# TFT_Interface.net
KiCad netlist of a schematic drawn in EAGLE
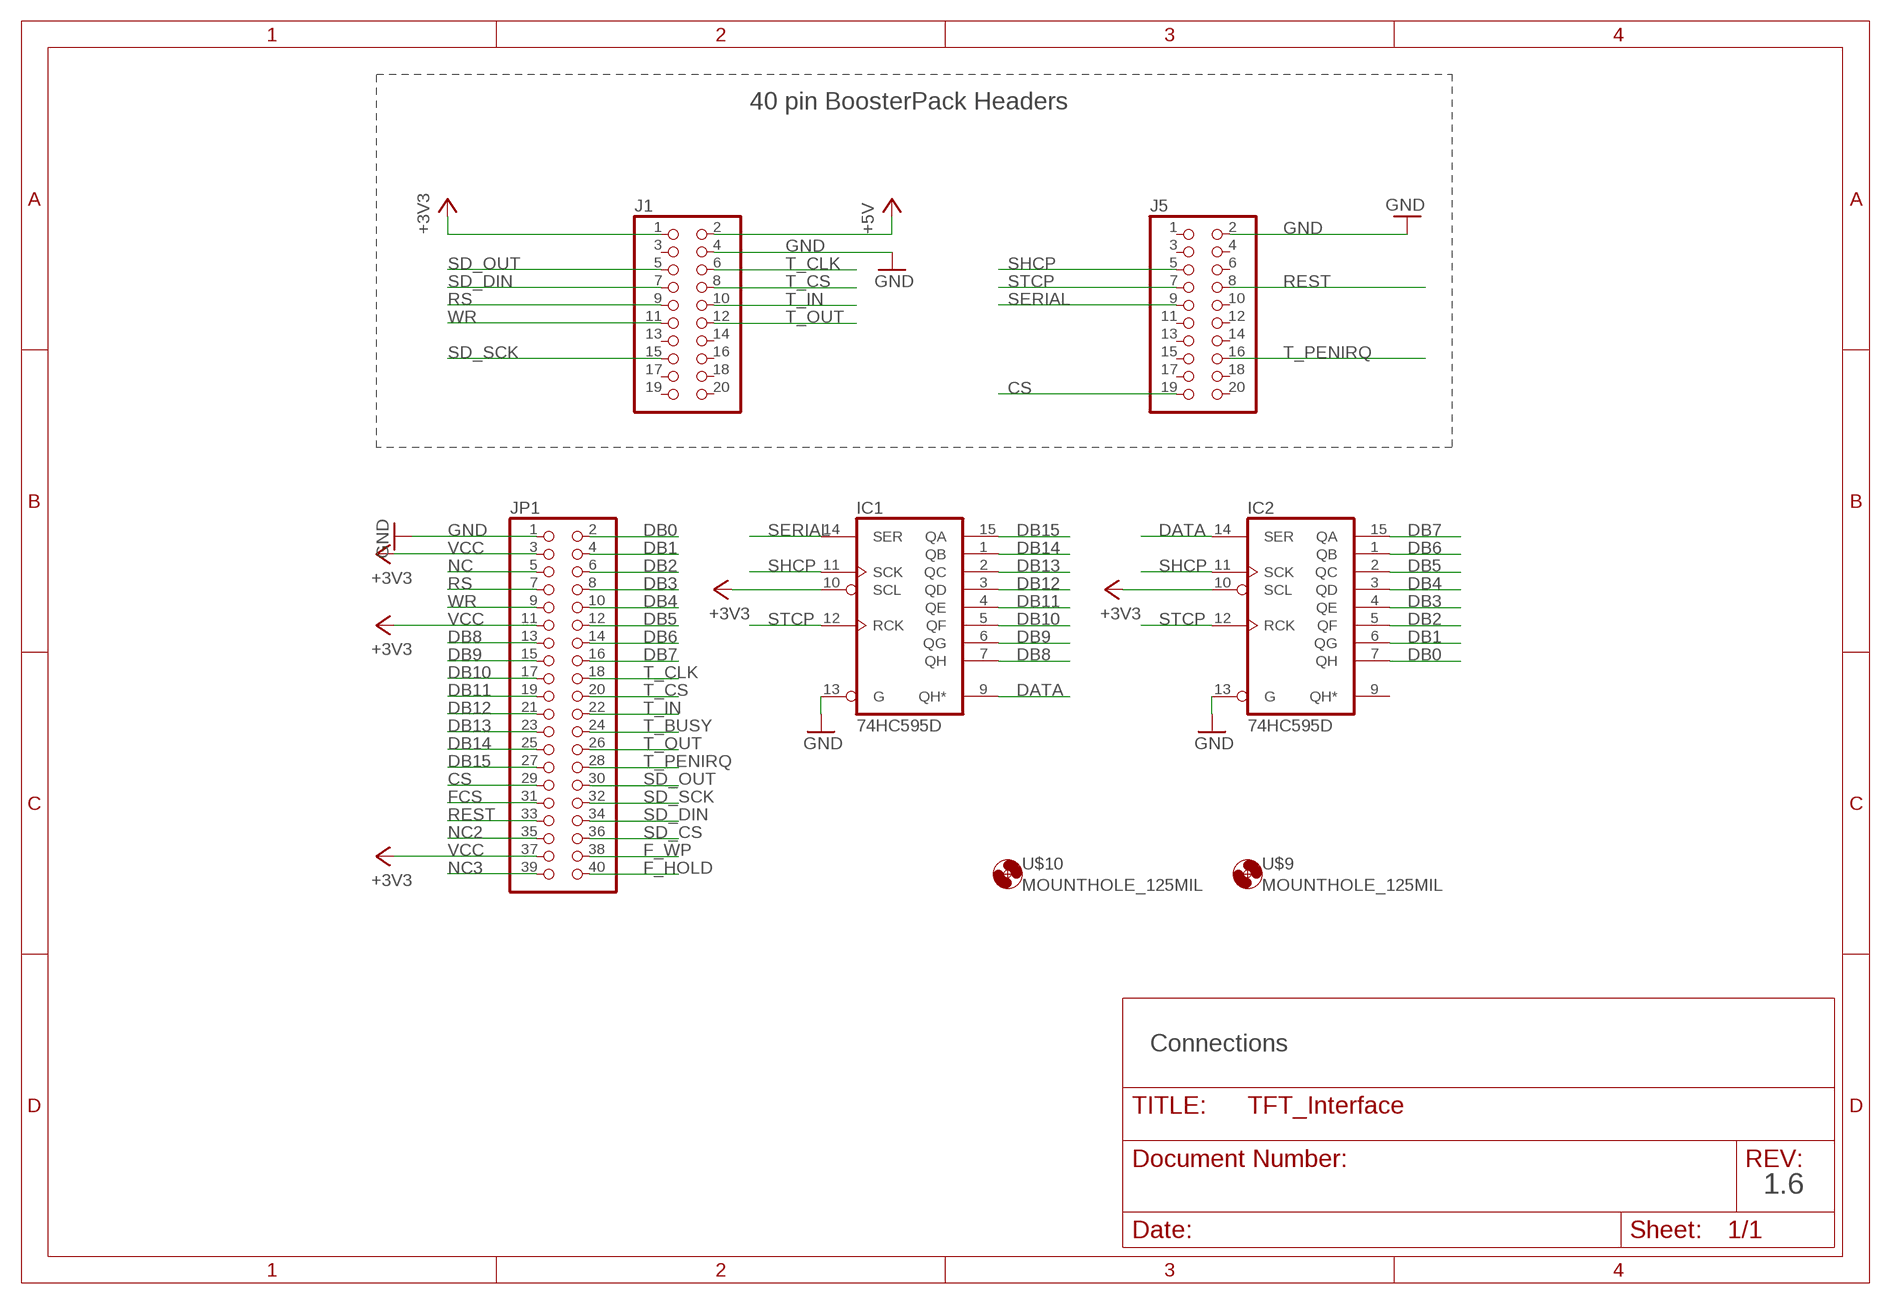
[diagram p0: schematic, sheet 1]

(export (version "E")
  (design (tool "Eeschema 10.0.6"))
  (components
    (comp (ref "IC1")
      (value "74HC595D")
      (footprint "eagle-import:SO16")
      (libsource (lib "eagle-import") (part "74595DHC"))
    )
    (comp (ref "IC2")
      (value "74HC595D")
      (footprint "eagle-import:SO16")
      (libsource (lib "eagle-import") (part "74595DHC"))
    )
    (comp (ref "J1")
      (value "PINHD-2X10")
      (footprint "eagle-import:2X10")
      (libsource (lib "eagle-import") (part "PINHD-2X10"))
    )
    (comp (ref "J5")
      (value "PINHD-2X10")
      (footprint "eagle-import:2X10")
      (libsource (lib "eagle-import") (part "PINHD-2X10"))
    )
    (comp (ref "JP1")
      (value "PINHD-2X20")
      (footprint "eagle-import:2X20")
      (libsource (lib "eagle-import") (part "PINHD-2X20"))
    )
    (comp (ref "U$9")
      (value "MOUNTHOLE_125MIL")
      (footprint "eagle-import:MOUNTHOLE_125MIL")
      (libsource (lib "eagle-import") (part "MOUNTHOLE_125MIL"))
    )
    (comp (ref "U$10")
      (value "MOUNTHOLE_125MIL")
      (footprint "eagle-import:MOUNTHOLE_125MIL")
      (libsource (lib "eagle-import") (part "MOUNTHOLE_125MIL"))
    )
  )
  (nets
    (net (code "1") (name "+3V3") (class "Default")
      (node (ref "IC1") (pin "10") (pinfunction "SCL_10") (pintype "input"))
      (node (ref "IC2") (pin "10") (pinfunction "SCL_10") (pintype "input"))
      (node (ref "J1") (pin "1") (pinfunction "1_1") (pintype "passive"))
      (node (ref "JP1") (pin "11") (pinfunction "11_11") (pintype "passive"))
      (node (ref "JP1") (pin "3") (pinfunction "3_3") (pintype "passive"))
      (node (ref "JP1") (pin "37") (pinfunction "37_37") (pintype "passive"))
    )
    (net (code "2") (name "+5V") (class "Default")
      (node (ref "J1") (pin "2") (pinfunction "2_2") (pintype "passive"))
    )
    (net (code "3") (name "/CS") (class "Default")
      (node (ref "J5") (pin "19") (pinfunction "19_19") (pintype "passive"))
      (node (ref "JP1") (pin "29") (pinfunction "29_29") (pintype "passive"))
    )
    (net (code "4") (name "/DATA") (class "Default")
      (node (ref "IC1") (pin "9") (pinfunction "QH*_9") (pintype "tri_state"))
      (node (ref "IC2") (pin "14") (pinfunction "SER_14") (pintype "input"))
    )
    (net (code "5") (name "/DB0") (class "Default")
      (node (ref "IC2") (pin "7") (pinfunction "QH_7") (pintype "tri_state"))
      (node (ref "JP1") (pin "2") (pinfunction "2_2") (pintype "passive"))
    )
    (net (code "6") (name "/DB1") (class "Default")
      (node (ref "IC2") (pin "6") (pinfunction "QG_6") (pintype "tri_state"))
      (node (ref "JP1") (pin "4") (pinfunction "4_4") (pintype "passive"))
    )
    (net (code "7") (name "/DB2") (class "Default")
      (node (ref "IC2") (pin "5") (pinfunction "QF_5") (pintype "tri_state"))
      (node (ref "JP1") (pin "6") (pinfunction "6_6") (pintype "passive"))
    )
    (net (code "8") (name "/DB3") (class "Default")
      (node (ref "IC2") (pin "4") (pinfunction "QE_4") (pintype "tri_state"))
      (node (ref "JP1") (pin "8") (pinfunction "8_8") (pintype "passive"))
    )
    (net (code "9") (name "/DB4") (class "Default")
      (node (ref "IC2") (pin "3") (pinfunction "QD_3") (pintype "tri_state"))
      (node (ref "JP1") (pin "10") (pinfunction "10_10") (pintype "passive"))
    )
    (net (code "10") (name "/DB5") (class "Default")
      (node (ref "IC2") (pin "2") (pinfunction "QC_2") (pintype "tri_state"))
      (node (ref "JP1") (pin "12") (pinfunction "12_12") (pintype "passive"))
    )
    (net (code "11") (name "/DB6") (class "Default")
      (node (ref "IC2") (pin "1") (pinfunction "QB_1") (pintype "tri_state"))
      (node (ref "JP1") (pin "14") (pinfunction "14_14") (pintype "passive"))
    )
    (net (code "12") (name "/DB7") (class "Default")
      (node (ref "IC2") (pin "15") (pinfunction "QA_15") (pintype "tri_state"))
      (node (ref "JP1") (pin "16") (pinfunction "16_16") (pintype "passive"))
    )
    (net (code "13") (name "/DB8") (class "Default")
      (node (ref "IC1") (pin "7") (pinfunction "QH_7") (pintype "tri_state"))
      (node (ref "JP1") (pin "13") (pinfunction "13_13") (pintype "passive"))
    )
    (net (code "14") (name "/DB9") (class "Default")
      (node (ref "IC1") (pin "6") (pinfunction "QG_6") (pintype "tri_state"))
      (node (ref "JP1") (pin "15") (pinfunction "15_15") (pintype "passive"))
    )
    (net (code "15") (name "/DB10") (class "Default")
      (node (ref "IC1") (pin "5") (pinfunction "QF_5") (pintype "tri_state"))
      (node (ref "JP1") (pin "17") (pinfunction "17_17") (pintype "passive"))
    )
    (net (code "16") (name "/DB11") (class "Default")
      (node (ref "IC1") (pin "4") (pinfunction "QE_4") (pintype "tri_state"))
      (node (ref "JP1") (pin "19") (pinfunction "19_19") (pintype "passive"))
    )
    (net (code "17") (name "/DB12") (class "Default")
      (node (ref "IC1") (pin "3") (pinfunction "QD_3") (pintype "tri_state"))
      (node (ref "JP1") (pin "21") (pinfunction "21_21") (pintype "passive"))
    )
    (net (code "18") (name "/DB13") (class "Default")
      (node (ref "IC1") (pin "2") (pinfunction "QC_2") (pintype "tri_state"))
      (node (ref "JP1") (pin "23") (pinfunction "23_23") (pintype "passive"))
    )
    (net (code "19") (name "/DB14") (class "Default")
      (node (ref "IC1") (pin "1") (pinfunction "QB_1") (pintype "tri_state"))
      (node (ref "JP1") (pin "25") (pinfunction "25_25") (pintype "passive"))
    )
    (net (code "20") (name "/DB15") (class "Default")
      (node (ref "IC1") (pin "15") (pinfunction "QA_15") (pintype "tri_state"))
      (node (ref "JP1") (pin "27") (pinfunction "27_27") (pintype "passive"))
    )
    (net (code "21") (name "/FCS") (class "Default")
      (node (ref "JP1") (pin "31") (pinfunction "31_31") (pintype "passive"))
    )
    (net (code "22") (name "/F_HOLD") (class "Default")
      (node (ref "JP1") (pin "40") (pinfunction "40_40") (pintype "passive"))
    )
    (net (code "23") (name "/F_WP") (class "Default")
      (node (ref "JP1") (pin "38") (pinfunction "38_38") (pintype "passive"))
    )
    (net (code "24") (name "/NC") (class "Default")
      (node (ref "JP1") (pin "5") (pinfunction "5_5") (pintype "passive"))
    )
    (net (code "25") (name "/NC2") (class "Default")
      (node (ref "JP1") (pin "35") (pinfunction "35_35") (pintype "passive"))
    )
    (net (code "26") (name "/NC3") (class "Default")
      (node (ref "JP1") (pin "39") (pinfunction "39_39") (pintype "passive"))
    )
    (net (code "27") (name "/REST") (class "Default")
      (node (ref "J5") (pin "8") (pinfunction "8_8") (pintype "passive"))
      (node (ref "JP1") (pin "33") (pinfunction "33_33") (pintype "passive"))
    )
    (net (code "28") (name "/RS") (class "Default")
      (node (ref "J1") (pin "9") (pinfunction "9_9") (pintype "passive"))
      (node (ref "JP1") (pin "7") (pinfunction "7_7") (pintype "passive"))
    )
    (net (code "29") (name "/SD_CS") (class "Default")
      (node (ref "JP1") (pin "36") (pinfunction "36_36") (pintype "passive"))
    )
    (net (code "30") (name "/SD_DIN") (class "Default")
      (node (ref "J1") (pin "7") (pinfunction "7_7") (pintype "passive"))
      (node (ref "JP1") (pin "34") (pinfunction "34_34") (pintype "passive"))
    )
    (net (code "31") (name "/SD_OUT") (class "Default")
      (node (ref "J1") (pin "5") (pinfunction "5_5") (pintype "passive"))
      (node (ref "JP1") (pin "30") (pinfunction "30_30") (pintype "passive"))
    )
    (net (code "32") (name "/SD_SCK") (class "Default")
      (node (ref "J1") (pin "15") (pinfunction "15_15") (pintype "passive"))
      (node (ref "JP1") (pin "32") (pinfunction "32_32") (pintype "passive"))
    )
    (net (code "33") (name "/SERIAL") (class "Default")
      (node (ref "IC1") (pin "14") (pinfunction "SER_14") (pintype "input"))
      (node (ref "J5") (pin "9") (pinfunction "9_9") (pintype "passive"))
    )
    (net (code "34") (name "/SHCP") (class "Default")
      (node (ref "IC1") (pin "11") (pinfunction "SCK_11") (pintype "input"))
      (node (ref "IC2") (pin "11") (pinfunction "SCK_11") (pintype "input"))
      (node (ref "J5") (pin "5") (pinfunction "5_5") (pintype "passive"))
    )
    (net (code "35") (name "/STCP") (class "Default")
      (node (ref "IC1") (pin "12") (pinfunction "RCK_12") (pintype "input"))
      (node (ref "IC2") (pin "12") (pinfunction "RCK_12") (pintype "input"))
      (node (ref "J5") (pin "7") (pinfunction "7_7") (pintype "passive"))
    )
    (net (code "36") (name "/T_BUSY") (class "Default")
      (node (ref "JP1") (pin "24") (pinfunction "24_24") (pintype "passive"))
    )
    (net (code "37") (name "/T_CLK") (class "Default")
      (node (ref "J1") (pin "6") (pinfunction "6_6") (pintype "passive"))
      (node (ref "JP1") (pin "18") (pinfunction "18_18") (pintype "passive"))
    )
    (net (code "38") (name "/T_CS") (class "Default")
      (node (ref "J1") (pin "8") (pinfunction "8_8") (pintype "passive"))
      (node (ref "JP1") (pin "20") (pinfunction "20_20") (pintype "passive"))
    )
    (net (code "39") (name "/T_IN") (class "Default")
      (node (ref "J1") (pin "10") (pinfunction "10_10") (pintype "passive"))
      (node (ref "JP1") (pin "22") (pinfunction "22_22") (pintype "passive"))
    )
    (net (code "40") (name "/T_OUT") (class "Default")
      (node (ref "J1") (pin "12") (pinfunction "12_12") (pintype "passive"))
      (node (ref "JP1") (pin "26") (pinfunction "26_26") (pintype "passive"))
    )
    (net (code "41") (name "/T_PENIRQ") (class "Default")
      (node (ref "J5") (pin "16") (pinfunction "16_16") (pintype "passive"))
      (node (ref "JP1") (pin "28") (pinfunction "28_28") (pintype "passive"))
    )
    (net (code "42") (name "/WR") (class "Default")
      (node (ref "J1") (pin "11") (pinfunction "11_11") (pintype "passive"))
      (node (ref "JP1") (pin "9") (pinfunction "9_9") (pintype "passive"))
    )
    (net (code "43") (name "GND") (class "Default")
      (node (ref "IC1") (pin "13") (pinfunction "G_13") (pintype "input"))
      (node (ref "IC2") (pin "13") (pinfunction "G_13") (pintype "input"))
      (node (ref "J1") (pin "4") (pinfunction "4_4") (pintype "passive"))
      (node (ref "J5") (pin "2") (pinfunction "2_2") (pintype "passive"))
      (node (ref "JP1") (pin "1") (pinfunction "1_1") (pintype "passive"))
    )
    (net (code "44") (name "unconnected-(IC2A-QH*-Pad9)") (class "Default")
      (node (ref "IC2") (pin "9") (pinfunction "QH*_9") (pintype "tri_state"))
    )
    (net (code "45") (name "unconnected-(J1-Pad3)") (class "Default")
      (node (ref "J1") (pin "3") (pinfunction "3_3") (pintype "passive"))
    )
    (net (code "46") (name "unconnected-(J1-Pad13)") (class "Default")
      (node (ref "J1") (pin "13") (pinfunction "13_13") (pintype "passive"))
    )
    (net (code "47") (name "unconnected-(J1-Pad14)") (class "Default")
      (node (ref "J1") (pin "14") (pinfunction "14_14") (pintype "passive"))
    )
    (net (code "48") (name "unconnected-(J1-Pad16)") (class "Default")
      (node (ref "J1") (pin "16") (pinfunction "16_16") (pintype "passive"))
    )
    (net (code "49") (name "unconnected-(J1-Pad17)") (class "Default")
      (node (ref "J1") (pin "17") (pinfunction "17_17") (pintype "passive"))
    )
    (net (code "50") (name "unconnected-(J1-Pad18)") (class "Default")
      (node (ref "J1") (pin "18") (pinfunction "18_18") (pintype "passive"))
    )
    (net (code "51") (name "unconnected-(J1-Pad19)") (class "Default")
      (node (ref "J1") (pin "19") (pinfunction "19_19") (pintype "passive"))
    )
    (net (code "52") (name "unconnected-(J1-Pad20)") (class "Default")
      (node (ref "J1") (pin "20") (pinfunction "20_20") (pintype "passive"))
    )
    (net (code "53") (name "unconnected-(J5-Pad1)") (class "Default")
      (node (ref "J5") (pin "1") (pinfunction "1_1") (pintype "passive"))
    )
    (net (code "54") (name "unconnected-(J5-Pad3)") (class "Default")
      (node (ref "J5") (pin "3") (pinfunction "3_3") (pintype "passive"))
    )
    (net (code "55") (name "unconnected-(J5-Pad4)") (class "Default")
      (node (ref "J5") (pin "4") (pinfunction "4_4") (pintype "passive"))
    )
    (net (code "56") (name "unconnected-(J5-Pad6)") (class "Default")
      (node (ref "J5") (pin "6") (pinfunction "6_6") (pintype "passive"))
    )
    (net (code "57") (name "unconnected-(J5-Pad10)") (class "Default")
      (node (ref "J5") (pin "10") (pinfunction "10_10") (pintype "passive"))
    )
    (net (code "58") (name "unconnected-(J5-Pad11)") (class "Default")
      (node (ref "J5") (pin "11") (pinfunction "11_11") (pintype "passive"))
    )
    (net (code "59") (name "unconnected-(J5-Pad12)") (class "Default")
      (node (ref "J5") (pin "12") (pinfunction "12_12") (pintype "passive"))
    )
    (net (code "60") (name "unconnected-(J5-Pad13)") (class "Default")
      (node (ref "J5") (pin "13") (pinfunction "13_13") (pintype "passive"))
    )
    (net (code "61") (name "unconnected-(J5-Pad14)") (class "Default")
      (node (ref "J5") (pin "14") (pinfunction "14_14") (pintype "passive"))
    )
    (net (code "62") (name "unconnected-(J5-Pad15)") (class "Default")
      (node (ref "J5") (pin "15") (pinfunction "15_15") (pintype "passive"))
    )
    (net (code "63") (name "unconnected-(J5-Pad17)") (class "Default")
      (node (ref "J5") (pin "17") (pinfunction "17_17") (pintype "passive"))
    )
    (net (code "64") (name "unconnected-(J5-Pad18)") (class "Default")
      (node (ref "J5") (pin "18") (pinfunction "18_18") (pintype "passive"))
    )
    (net (code "65") (name "unconnected-(J5-Pad20)") (class "Default")
      (node (ref "J5") (pin "20") (pinfunction "20_20") (pintype "passive"))
    )
  )
)
